# Circuit_de_priorit.net
KiCad netlist of a schematic drawn in Altium Designer
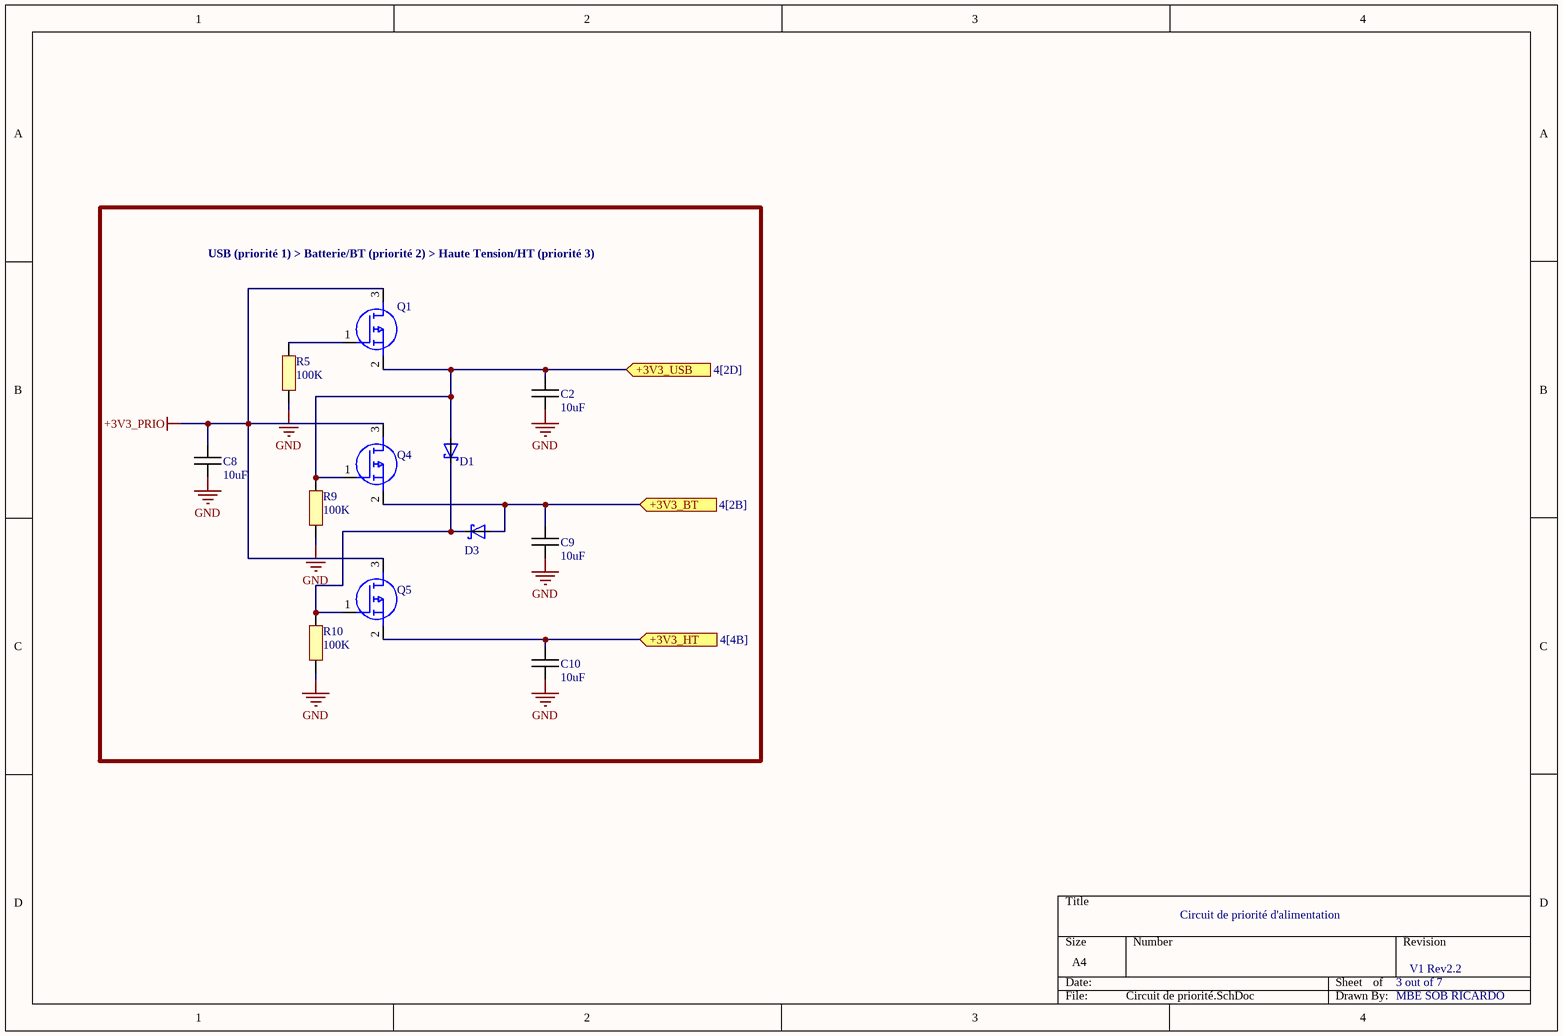
[diagram p0: Circuit de priorité.SchDoc]

(export (version "E")
  (design (tool "Eeschema 10.0.6"))
  (components
    (comp (ref "C2")
      (value "10uF")
      (footprint "CAPC1005X06N")
      (libsource (lib "SCHLibrary") (part "Capacitor"))
    )
    (comp (ref "C8")
      (value "10uF")
      (footprint "CAPC1005X06N")
      (libsource (lib "SCHLibrary") (part "Capacitor"))
    )
    (comp (ref "C9")
      (value "10uF")
      (footprint "CAPC1005X06N")
      (libsource (lib "SCHLibrary") (part "Capacitor"))
    )
    (comp (ref "C10")
      (value "10uF")
      (footprint "CAPC1005X06N")
      (libsource (lib "SCHLibrary") (part "Capacitor"))
    )
    (comp (ref "D1")
      (value "SD103AWS-7-F")
      (footprint "SD103AWS-7-F")
      (description "Diode Array 3 Independent Schottky 40V 175mA Surface Mount 6-TSSOP, SC-88, SOT-363")
      (libsource (lib "SCHLibrary") (part "SD103AWS-7-F"))
    )
    (comp (ref "D3")
      (value "SD103AWS-7-F")
      (footprint "SD103AWS-7-F")
      (description "Diode Array 3 Independent Schottky 40V 175mA Surface Mount 6-TSSOP, SC-88, SOT-363")
      (libsource (lib "SCHLibrary") (part "SD103AWS-7-F"))
    )
    (comp (ref "Q1")
      (value "SI3139K-TP")
      (footprint "SI3139K-TP")
      (description "MOSFET P-Channel MOSFET")
      (libsource (lib "SCHLibrary") (part "SI3139K-TP"))
    )
    (comp (ref "Q4")
      (value "SI3139K-TP")
      (footprint "SI3139K-TP")
      (description "MOSFET P-Channel MOSFET")
      (libsource (lib "SCHLibrary") (part "SI3139K-TP"))
    )
    (comp (ref "Q5")
      (value "SI3139K-TP")
      (footprint "SI3139K-TP")
      (description "MOSFET P-Channel MOSFET")
      (libsource (lib "SCHLibrary") (part "SI3139K-TP"))
    )
    (comp (ref "R5")
      (value "100K")
      (footprint "RESC1005X06N")
      (libsource (lib "SCHLibrary") (part "Resistor"))
    )
    (comp (ref "R9")
      (value "100K")
      (footprint "RESC1005X06N")
      (libsource (lib "SCHLibrary") (part "Resistor"))
    )
    (comp (ref "R10")
      (value "100K")
      (footprint "RESC1005X06N")
      (libsource (lib "SCHLibrary") (part "Resistor"))
    )
  )
  (nets
    (net (code "1") (name "+3V3_PRIO") (class "Default")
      (node (ref "C8") (pin "1") (pinfunction "1_1") (pintype "passive"))
      (node (ref "Q1") (pin "3") (pinfunction "D_3") (pintype "passive"))
      (node (ref "Q4") (pin "3") (pinfunction "D_3") (pintype "passive"))
      (node (ref "Q5") (pin "3") (pinfunction "D_3") (pintype "passive"))
    )
    (net (code "2") (name "/+3V3_BT") (class "Default")
      (node (ref "C9") (pin "1") (pinfunction "1_1") (pintype "passive"))
      (node (ref "D3") (pin "2") (pinfunction "A_2") (pintype "passive"))
      (node (ref "Q4") (pin "2") (pinfunction "S_2") (pintype "passive"))
    )
    (net (code "3") (name "/+3V3_HT") (class "Default")
      (node (ref "C10") (pin "1") (pinfunction "1_1") (pintype "passive"))
      (node (ref "Q5") (pin "2") (pinfunction "S_2") (pintype "passive"))
    )
    (net (code "4") (name "/+3V3_USB") (class "Default")
      (node (ref "C2") (pin "1") (pinfunction "1_1") (pintype "passive"))
      (node (ref "D1") (pin "2") (pinfunction "A_2") (pintype "passive"))
      (node (ref "Q1") (pin "2") (pinfunction "S_2") (pintype "passive"))
      (node (ref "Q4") (pin "1") (pinfunction "G_1") (pintype "passive"))
      (node (ref "R9") (pin "1") (pinfunction "1_1") (pintype "passive"))
    )
    (net (code "5") (name "GND") (class "Default")
      (node (ref "C10") (pin "2") (pinfunction "2_2") (pintype "passive"))
      (node (ref "C2") (pin "2") (pinfunction "2_2") (pintype "passive"))
      (node (ref "C8") (pin "2") (pinfunction "2_2") (pintype "passive"))
      (node (ref "C9") (pin "2") (pinfunction "2_2") (pintype "passive"))
      (node (ref "R10") (pin "2") (pinfunction "2_2") (pintype "passive"))
      (node (ref "R5") (pin "2") (pinfunction "2_2") (pintype "passive"))
      (node (ref "R9") (pin "2") (pinfunction "2_2") (pintype "passive"))
    )
    (net (code "6") (name "Net-(D1-C)") (class "Default")
      (node (ref "D1") (pin "1") (pinfunction "C_1") (pintype "passive"))
      (node (ref "D3") (pin "1") (pinfunction "C_1") (pintype "passive"))
      (node (ref "Q5") (pin "1") (pinfunction "G_1") (pintype "passive"))
      (node (ref "R10") (pin "1") (pinfunction "1_1") (pintype "passive"))
    )
    (net (code "7") (name "Net-(Q1-G)") (class "Default")
      (node (ref "Q1") (pin "1") (pinfunction "G_1") (pintype "passive"))
      (node (ref "R5") (pin "1") (pinfunction "1_1") (pintype "passive"))
    )
  )
)
